# h_bridge_shield.net
KiCad netlist of a schematic drawn in EAGLE
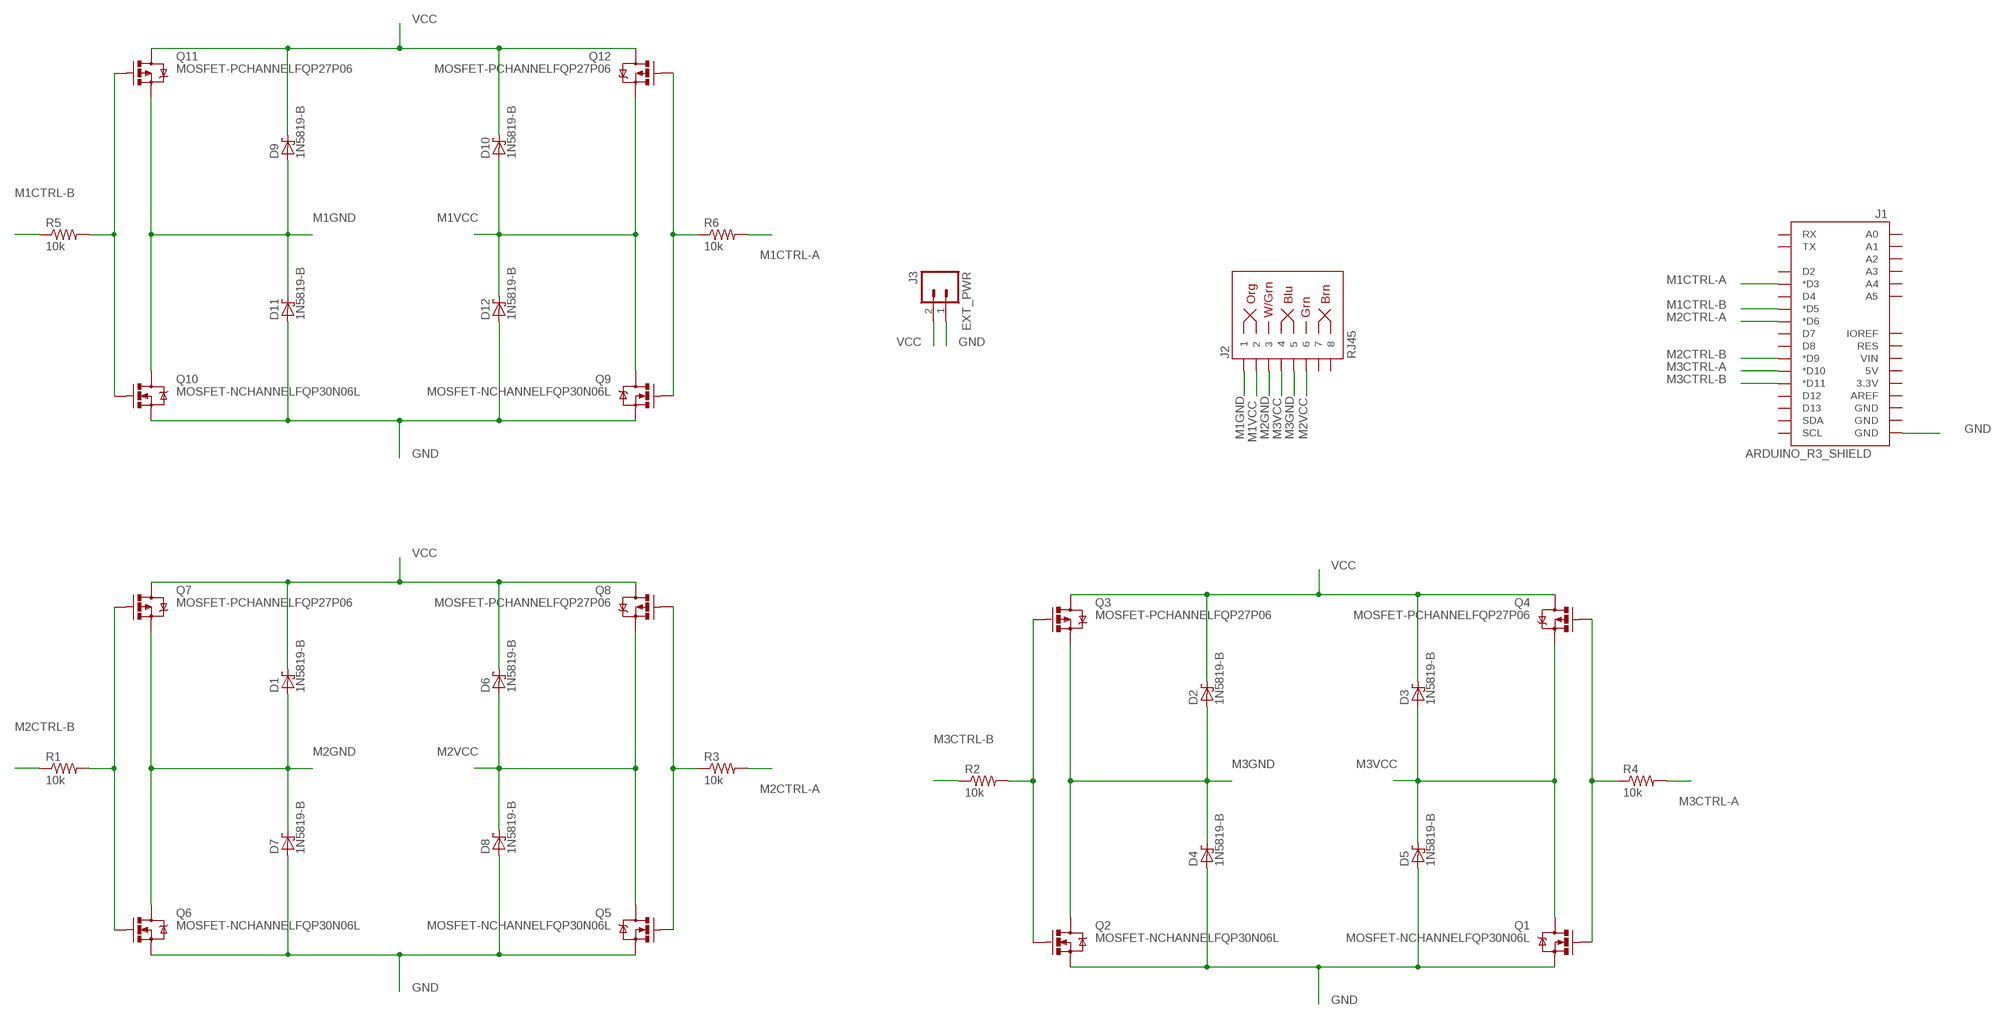
[diagram p0: schematic, sheet 1]

(export (version "E")
  (design (tool "Eeschema 10.0.6"))
  (components
    (comp (ref "D1")
      (value "1N5819-B")
      (footprint "eagle-import:DO41-7.6")
      (libsource (lib "eagle-import") (part "1N5819-B"))
    )
    (comp (ref "D2")
      (value "1N5819-B")
      (footprint "eagle-import:DO41-7.6")
      (libsource (lib "eagle-import") (part "1N5819-B"))
    )
    (comp (ref "D3")
      (value "1N5819-B")
      (footprint "eagle-import:DO41-7.6")
      (libsource (lib "eagle-import") (part "1N5819-B"))
    )
    (comp (ref "D4")
      (value "1N5819-B")
      (footprint "eagle-import:DO41-7.6")
      (libsource (lib "eagle-import") (part "1N5819-B"))
    )
    (comp (ref "D5")
      (value "1N5819-B")
      (footprint "eagle-import:DO41-7.6")
      (libsource (lib "eagle-import") (part "1N5819-B"))
    )
    (comp (ref "D6")
      (value "1N5819-B")
      (footprint "eagle-import:DO41-7.6")
      (libsource (lib "eagle-import") (part "1N5819-B"))
    )
    (comp (ref "D7")
      (value "1N5819-B")
      (footprint "eagle-import:DO41-7.6")
      (libsource (lib "eagle-import") (part "1N5819-B"))
    )
    (comp (ref "D8")
      (value "1N5819-B")
      (footprint "eagle-import:DO41-7.6")
      (libsource (lib "eagle-import") (part "1N5819-B"))
    )
    (comp (ref "D9")
      (value "1N5819-B")
      (footprint "eagle-import:DO41-7.6")
      (libsource (lib "eagle-import") (part "1N5819-B"))
    )
    (comp (ref "D10")
      (value "1N5819-B")
      (footprint "eagle-import:DO41-7.6")
      (libsource (lib "eagle-import") (part "1N5819-B"))
    )
    (comp (ref "D11")
      (value "1N5819-B")
      (footprint "eagle-import:DO41-7.6")
      (libsource (lib "eagle-import") (part "1N5819-B"))
    )
    (comp (ref "D12")
      (value "1N5819-B")
      (footprint "eagle-import:DO41-7.6")
      (libsource (lib "eagle-import") (part "1N5819-B"))
    )
    (comp (ref "J1")
      (value "ARDUINO_R3_SHIELD")
      (footprint "eagle-import:UNO_R3_SHIELD")
      (libsource (lib "eagle-import") (part "ARDUINO_R3_SHIELD"))
    )
    (comp (ref "J2")
      (value "RJ45")
      (footprint "eagle-import:RJ45-8")
      (libsource (lib "eagle-import") (part "RJ45-8PTH"))
    )
    (comp (ref "J3")
      (value "EXT_PWR")
      (footprint "eagle-import:JST-2-PTH-VERT")
      (libsource (lib "eagle-import") (part "M02JST-PTH-VERT"))
    )
    (comp (ref "Q1")
      (value "MOSFET-NCHANNELFQP30N06L")
      (footprint "eagle-import:TO220V")
      (libsource (lib "eagle-import") (part "MOSFET-NCHANNELFQP30N06L"))
    )
    (comp (ref "Q2")
      (value "MOSFET-NCHANNELFQP30N06L")
      (footprint "eagle-import:TO220V")
      (libsource (lib "eagle-import") (part "MOSFET-NCHANNELFQP30N06L"))
    )
    (comp (ref "Q3")
      (value "MOSFET-PCHANNELFQP27P06")
      (footprint "eagle-import:TO220V")
      (libsource (lib "eagle-import") (part "MOSFET-PCHANNELFQP27P06"))
    )
    (comp (ref "Q4")
      (value "MOSFET-PCHANNELFQP27P06")
      (footprint "eagle-import:TO220V")
      (libsource (lib "eagle-import") (part "MOSFET-PCHANNELFQP27P06"))
    )
    (comp (ref "Q5")
      (value "MOSFET-NCHANNELFQP30N06L")
      (footprint "eagle-import:TO220V")
      (libsource (lib "eagle-import") (part "MOSFET-NCHANNELFQP30N06L"))
    )
    (comp (ref "Q6")
      (value "MOSFET-NCHANNELFQP30N06L")
      (footprint "eagle-import:TO220V")
      (libsource (lib "eagle-import") (part "MOSFET-NCHANNELFQP30N06L"))
    )
    (comp (ref "Q7")
      (value "MOSFET-PCHANNELFQP27P06")
      (footprint "eagle-import:TO220V")
      (libsource (lib "eagle-import") (part "MOSFET-PCHANNELFQP27P06"))
    )
    (comp (ref "Q8")
      (value "MOSFET-PCHANNELFQP27P06")
      (footprint "eagle-import:TO220V")
      (libsource (lib "eagle-import") (part "MOSFET-PCHANNELFQP27P06"))
    )
    (comp (ref "Q9")
      (value "MOSFET-NCHANNELFQP30N06L")
      (footprint "eagle-import:TO220V")
      (libsource (lib "eagle-import") (part "MOSFET-NCHANNELFQP30N06L"))
    )
    (comp (ref "Q10")
      (value "MOSFET-NCHANNELFQP30N06L")
      (footprint "eagle-import:TO220V")
      (libsource (lib "eagle-import") (part "MOSFET-NCHANNELFQP30N06L"))
    )
    (comp (ref "Q11")
      (value "MOSFET-PCHANNELFQP27P06")
      (footprint "eagle-import:TO220V")
      (libsource (lib "eagle-import") (part "MOSFET-PCHANNELFQP27P06"))
    )
    (comp (ref "Q12")
      (value "MOSFET-PCHANNELFQP27P06")
      (footprint "eagle-import:TO220V")
      (libsource (lib "eagle-import") (part "MOSFET-PCHANNELFQP27P06"))
    )
    (comp (ref "R1")
      (value "10k")
      (footprint "eagle-import:AXIAL-0.3")
      (libsource (lib "eagle-import") (part "10KOHM-1/4W5%(PTH)"))
    )
    (comp (ref "R2")
      (value "10k")
      (footprint "eagle-import:AXIAL-0.3")
      (libsource (lib "eagle-import") (part "10KOHM-1/4W5%(PTH)"))
    )
    (comp (ref "R3")
      (value "10k")
      (footprint "eagle-import:AXIAL-0.3")
      (libsource (lib "eagle-import") (part "10KOHM-1/4W5%(PTH)"))
    )
    (comp (ref "R4")
      (value "10k")
      (footprint "eagle-import:AXIAL-0.3")
      (libsource (lib "eagle-import") (part "10KOHM-1/4W5%(PTH)"))
    )
    (comp (ref "R5")
      (value "10k")
      (footprint "eagle-import:AXIAL-0.3")
      (libsource (lib "eagle-import") (part "10KOHM-1/4W5%(PTH)"))
    )
    (comp (ref "R6")
      (value "10k")
      (footprint "eagle-import:AXIAL-0.3")
      (libsource (lib "eagle-import") (part "10KOHM-1/4W5%(PTH)"))
    )
  )
  (nets
    (net (code "1") (name "/GND") (class "Default")
      (node (ref "D11") (pin "A") (pinfunction "A_A") (pintype "passive"))
      (node (ref "D12") (pin "A") (pinfunction "A_A") (pintype "passive"))
      (node (ref "D4") (pin "A") (pinfunction "A_A") (pintype "passive"))
      (node (ref "D5") (pin "A") (pinfunction "A_A") (pintype "passive"))
      (node (ref "D7") (pin "A") (pinfunction "A_A") (pintype "passive"))
      (node (ref "D8") (pin "A") (pinfunction "A_A") (pintype "passive"))
      (node (ref "J1") (pin "GND@0") (pinfunction "GND_GND@0") (pintype "bidirectional"))
      (node (ref "J3") (pin "1") (pinfunction "1_1") (pintype "passive"))
      (node (ref "Q1") (pin "3") (pinfunction "S_3") (pintype "passive"))
      (node (ref "Q10") (pin "3") (pinfunction "S_3") (pintype "passive"))
      (node (ref "Q2") (pin "3") (pinfunction "S_3") (pintype "passive"))
      (node (ref "Q5") (pin "3") (pinfunction "S_3") (pintype "passive"))
      (node (ref "Q6") (pin "3") (pinfunction "S_3") (pintype "passive"))
      (node (ref "Q9") (pin "3") (pinfunction "S_3") (pintype "passive"))
    )
    (net (code "2") (name "/M1CTRL-A") (class "Default")
      (node (ref "J1") (pin "D3") (pinfunction "*D3_D3") (pintype "bidirectional"))
      (node (ref "R6") (pin "P$2") (pinfunction "2_P$2") (pintype "passive"))
    )
    (net (code "3") (name "/M1CTRL-B") (class "Default")
      (node (ref "J1") (pin "D5") (pinfunction "*D5_D5") (pintype "bidirectional"))
      (node (ref "R5") (pin "P$1") (pinfunction "1_P$1") (pintype "passive"))
    )
    (net (code "4") (name "/M1GND") (class "Default")
      (node (ref "D11") (pin "C") (pinfunction "C_C") (pintype "passive"))
      (node (ref "D9") (pin "A") (pinfunction "A_A") (pintype "passive"))
      (node (ref "J2") (pin "1") (pinfunction "1_1") (pintype "bidirectional"))
      (node (ref "Q10") (pin "2") (pinfunction "D_2") (pintype "passive"))
      (node (ref "Q11") (pin "3") (pinfunction "S_3") (pintype "passive"))
    )
    (net (code "5") (name "/M1VCC") (class "Default")
      (node (ref "D10") (pin "A") (pinfunction "A_A") (pintype "passive"))
      (node (ref "D12") (pin "C") (pinfunction "C_C") (pintype "passive"))
      (node (ref "J2") (pin "2") (pinfunction "2_2") (pintype "bidirectional"))
      (node (ref "Q12") (pin "3") (pinfunction "S_3") (pintype "passive"))
      (node (ref "Q9") (pin "2") (pinfunction "D_2") (pintype "passive"))
    )
    (net (code "6") (name "/M2CTRL-A") (class "Default")
      (node (ref "J1") (pin "D6") (pinfunction "*D6_D6") (pintype "bidirectional"))
      (node (ref "R3") (pin "P$2") (pinfunction "2_P$2") (pintype "passive"))
    )
    (net (code "7") (name "/M2CTRL-B") (class "Default")
      (node (ref "J1") (pin "D9") (pinfunction "*D9_D9") (pintype "bidirectional"))
      (node (ref "R1") (pin "P$1") (pinfunction "1_P$1") (pintype "passive"))
    )
    (net (code "8") (name "/M2GND") (class "Default")
      (node (ref "D1") (pin "A") (pinfunction "A_A") (pintype "passive"))
      (node (ref "D7") (pin "C") (pinfunction "C_C") (pintype "passive"))
      (node (ref "J2") (pin "3") (pinfunction "3_3") (pintype "bidirectional"))
      (node (ref "Q6") (pin "2") (pinfunction "D_2") (pintype "passive"))
      (node (ref "Q7") (pin "3") (pinfunction "S_3") (pintype "passive"))
    )
    (net (code "9") (name "/M2VCC") (class "Default")
      (node (ref "D6") (pin "A") (pinfunction "A_A") (pintype "passive"))
      (node (ref "D8") (pin "C") (pinfunction "C_C") (pintype "passive"))
      (node (ref "J2") (pin "6") (pinfunction "6_6") (pintype "bidirectional"))
      (node (ref "Q5") (pin "2") (pinfunction "D_2") (pintype "passive"))
      (node (ref "Q8") (pin "3") (pinfunction "S_3") (pintype "passive"))
    )
    (net (code "10") (name "/M3CTRL-A") (class "Default")
      (node (ref "J1") (pin "D10") (pinfunction "*D10_D10") (pintype "bidirectional"))
      (node (ref "R4") (pin "P$2") (pinfunction "2_P$2") (pintype "passive"))
    )
    (net (code "11") (name "/M3CTRL-B") (class "Default")
      (node (ref "J1") (pin "D11") (pinfunction "*D11_D11") (pintype "bidirectional"))
      (node (ref "R2") (pin "P$1") (pinfunction "1_P$1") (pintype "passive"))
    )
    (net (code "12") (name "/M3GND") (class "Default")
      (node (ref "D2") (pin "A") (pinfunction "A_A") (pintype "passive"))
      (node (ref "D4") (pin "C") (pinfunction "C_C") (pintype "passive"))
      (node (ref "J2") (pin "5") (pinfunction "5_5") (pintype "bidirectional"))
      (node (ref "Q2") (pin "2") (pinfunction "D_2") (pintype "passive"))
      (node (ref "Q3") (pin "3") (pinfunction "S_3") (pintype "passive"))
    )
    (net (code "13") (name "/M3VCC") (class "Default")
      (node (ref "D3") (pin "A") (pinfunction "A_A") (pintype "passive"))
      (node (ref "D5") (pin "C") (pinfunction "C_C") (pintype "passive"))
      (node (ref "J2") (pin "4") (pinfunction "4_4") (pintype "bidirectional"))
      (node (ref "Q1") (pin "2") (pinfunction "D_2") (pintype "passive"))
      (node (ref "Q4") (pin "3") (pinfunction "S_3") (pintype "passive"))
    )
    (net (code "14") (name "/VCC") (class "Default")
      (node (ref "D1") (pin "C") (pinfunction "C_C") (pintype "passive"))
      (node (ref "D10") (pin "C") (pinfunction "C_C") (pintype "passive"))
      (node (ref "D2") (pin "C") (pinfunction "C_C") (pintype "passive"))
      (node (ref "D3") (pin "C") (pinfunction "C_C") (pintype "passive"))
      (node (ref "D6") (pin "C") (pinfunction "C_C") (pintype "passive"))
      (node (ref "D9") (pin "C") (pinfunction "C_C") (pintype "passive"))
      (node (ref "J3") (pin "2") (pinfunction "2_2") (pintype "passive"))
      (node (ref "Q11") (pin "2") (pinfunction "D_2") (pintype "passive"))
      (node (ref "Q12") (pin "2") (pinfunction "D_2") (pintype "passive"))
      (node (ref "Q3") (pin "2") (pinfunction "D_2") (pintype "passive"))
      (node (ref "Q4") (pin "2") (pinfunction "D_2") (pintype "passive"))
      (node (ref "Q7") (pin "2") (pinfunction "D_2") (pintype "passive"))
      (node (ref "Q8") (pin "2") (pinfunction "D_2") (pintype "passive"))
    )
    (net (code "15") (name "Net-(Q1-G)") (class "Default")
      (node (ref "Q1") (pin "1") (pinfunction "G_1") (pintype "passive"))
      (node (ref "Q4") (pin "1") (pinfunction "G_1") (pintype "passive"))
      (node (ref "R4") (pin "P$1") (pinfunction "1_P$1") (pintype "passive"))
    )
    (net (code "16") (name "Net-(Q2-G)") (class "Default")
      (node (ref "Q2") (pin "1") (pinfunction "G_1") (pintype "passive"))
      (node (ref "Q3") (pin "1") (pinfunction "G_1") (pintype "passive"))
      (node (ref "R2") (pin "P$2") (pinfunction "2_P$2") (pintype "passive"))
    )
    (net (code "17") (name "Net-(Q5-G)") (class "Default")
      (node (ref "Q5") (pin "1") (pinfunction "G_1") (pintype "passive"))
      (node (ref "Q8") (pin "1") (pinfunction "G_1") (pintype "passive"))
      (node (ref "R3") (pin "P$1") (pinfunction "1_P$1") (pintype "passive"))
    )
    (net (code "18") (name "Net-(Q6-G)") (class "Default")
      (node (ref "Q6") (pin "1") (pinfunction "G_1") (pintype "passive"))
      (node (ref "Q7") (pin "1") (pinfunction "G_1") (pintype "passive"))
      (node (ref "R1") (pin "P$2") (pinfunction "2_P$2") (pintype "passive"))
    )
    (net (code "19") (name "Net-(Q10-G)") (class "Default")
      (node (ref "Q10") (pin "1") (pinfunction "G_1") (pintype "passive"))
      (node (ref "Q11") (pin "1") (pinfunction "G_1") (pintype "passive"))
      (node (ref "R5") (pin "P$2") (pinfunction "2_P$2") (pintype "passive"))
    )
    (net (code "20") (name "Net-(Q12-G)") (class "Default")
      (node (ref "Q12") (pin "1") (pinfunction "G_1") (pintype "passive"))
      (node (ref "Q9") (pin "1") (pinfunction "G_1") (pintype "passive"))
      (node (ref "R6") (pin "P$1") (pinfunction "1_P$1") (pintype "passive"))
    )
    (net (code "21") (name "unconnected-(J1-GND-PadGND@1)") (class "Default")
      (node (ref "J1") (pin "GND@1") (pinfunction "GND_GND@1") (pintype "bidirectional"))
    )
    (net (code "22") (name "unconnected-(J1-GND-PadGND@2)") (class "Default")
      (node (ref "J1") (pin "GND@2") (pinfunction "GND_GND@2") (pintype "bidirectional"))
    )
    (net (code "23") (name "unconnected-(J1-Pad3.3V)") (class "Default")
      (node (ref "J1") (pin "3.3V") (pinfunction "3.3V_3.3V") (pintype "bidirectional"))
    )
    (net (code "24") (name "unconnected-(J1-Pad5V)") (class "Default")
      (node (ref "J1") (pin "5V") (pinfunction "5V_5V") (pintype "bidirectional"))
    )
    (net (code "25") (name "unconnected-(J1-PadA0)") (class "Default")
      (node (ref "J1") (pin "A0") (pinfunction "A0_A0") (pintype "bidirectional"))
    )
    (net (code "26") (name "unconnected-(J1-PadA1)") (class "Default")
      (node (ref "J1") (pin "A1") (pinfunction "A1_A1") (pintype "bidirectional"))
    )
    (net (code "27") (name "unconnected-(J1-PadA2)") (class "Default")
      (node (ref "J1") (pin "A2") (pinfunction "A2_A2") (pintype "bidirectional"))
    )
    (net (code "28") (name "unconnected-(J1-PadA3)") (class "Default")
      (node (ref "J1") (pin "A3") (pinfunction "A3_A3") (pintype "bidirectional"))
    )
    (net (code "29") (name "unconnected-(J1-PadA4)") (class "Default")
      (node (ref "J1") (pin "A4") (pinfunction "A4_A4") (pintype "bidirectional"))
    )
    (net (code "30") (name "unconnected-(J1-PadA5)") (class "Default")
      (node (ref "J1") (pin "A5") (pinfunction "A5_A5") (pintype "bidirectional"))
    )
    (net (code "31") (name "unconnected-(J1-PadAREF)") (class "Default")
      (node (ref "J1") (pin "AREF") (pinfunction "AREF_AREF") (pintype "bidirectional"))
    )
    (net (code "32") (name "unconnected-(J1-PadD2)") (class "Default")
      (node (ref "J1") (pin "D2") (pinfunction "D2_D2") (pintype "bidirectional"))
    )
    (net (code "33") (name "unconnected-(J1-PadD4)") (class "Default")
      (node (ref "J1") (pin "D4") (pinfunction "D4_D4") (pintype "bidirectional"))
    )
    (net (code "34") (name "unconnected-(J1-PadD7)") (class "Default")
      (node (ref "J1") (pin "D7") (pinfunction "D7_D7") (pintype "bidirectional"))
    )
    (net (code "35") (name "unconnected-(J1-PadD8)") (class "Default")
      (node (ref "J1") (pin "D8") (pinfunction "D8_D8") (pintype "bidirectional"))
    )
    (net (code "36") (name "unconnected-(J1-PadD12)") (class "Default")
      (node (ref "J1") (pin "D12") (pinfunction "D12_D12") (pintype "bidirectional"))
    )
    (net (code "37") (name "unconnected-(J1-PadD13)") (class "Default")
      (node (ref "J1") (pin "D13") (pinfunction "D13_D13") (pintype "bidirectional"))
    )
    (net (code "38") (name "unconnected-(J1-PadIOREF)") (class "Default")
      (node (ref "J1") (pin "IOREF") (pinfunction "IOREF_IOREF") (pintype "bidirectional"))
    )
    (net (code "39") (name "unconnected-(J1-PadRES)") (class "Default")
      (node (ref "J1") (pin "RES") (pinfunction "RES_RES") (pintype "bidirectional"))
    )
    (net (code "40") (name "unconnected-(J1-PadRX)") (class "Default")
      (node (ref "J1") (pin "RX") (pinfunction "RX_RX") (pintype "bidirectional"))
    )
    (net (code "41") (name "unconnected-(J1-PadSCL)") (class "Default")
      (node (ref "J1") (pin "SCL") (pinfunction "SCL_SCL") (pintype "bidirectional"))
    )
    (net (code "42") (name "unconnected-(J1-PadSDA)") (class "Default")
      (node (ref "J1") (pin "SDA") (pinfunction "SDA_SDA") (pintype "bidirectional"))
    )
    (net (code "43") (name "unconnected-(J1-PadTX)") (class "Default")
      (node (ref "J1") (pin "TX") (pinfunction "TX_TX") (pintype "bidirectional"))
    )
    (net (code "44") (name "unconnected-(J1-PadVIN)") (class "Default")
      (node (ref "J1") (pin "VIN") (pinfunction "VIN_VIN") (pintype "bidirectional"))
    )
    (net (code "45") (name "unconnected-(J2-Pad7)") (class "Default")
      (node (ref "J2") (pin "7") (pinfunction "7_7") (pintype "bidirectional"))
    )
    (net (code "46") (name "unconnected-(J2-Pad8)") (class "Default")
      (node (ref "J2") (pin "8") (pinfunction "8_8") (pintype "bidirectional"))
    )
  )
)
